# v13.net
KiCad netlist of a schematic drawn in EAGLE
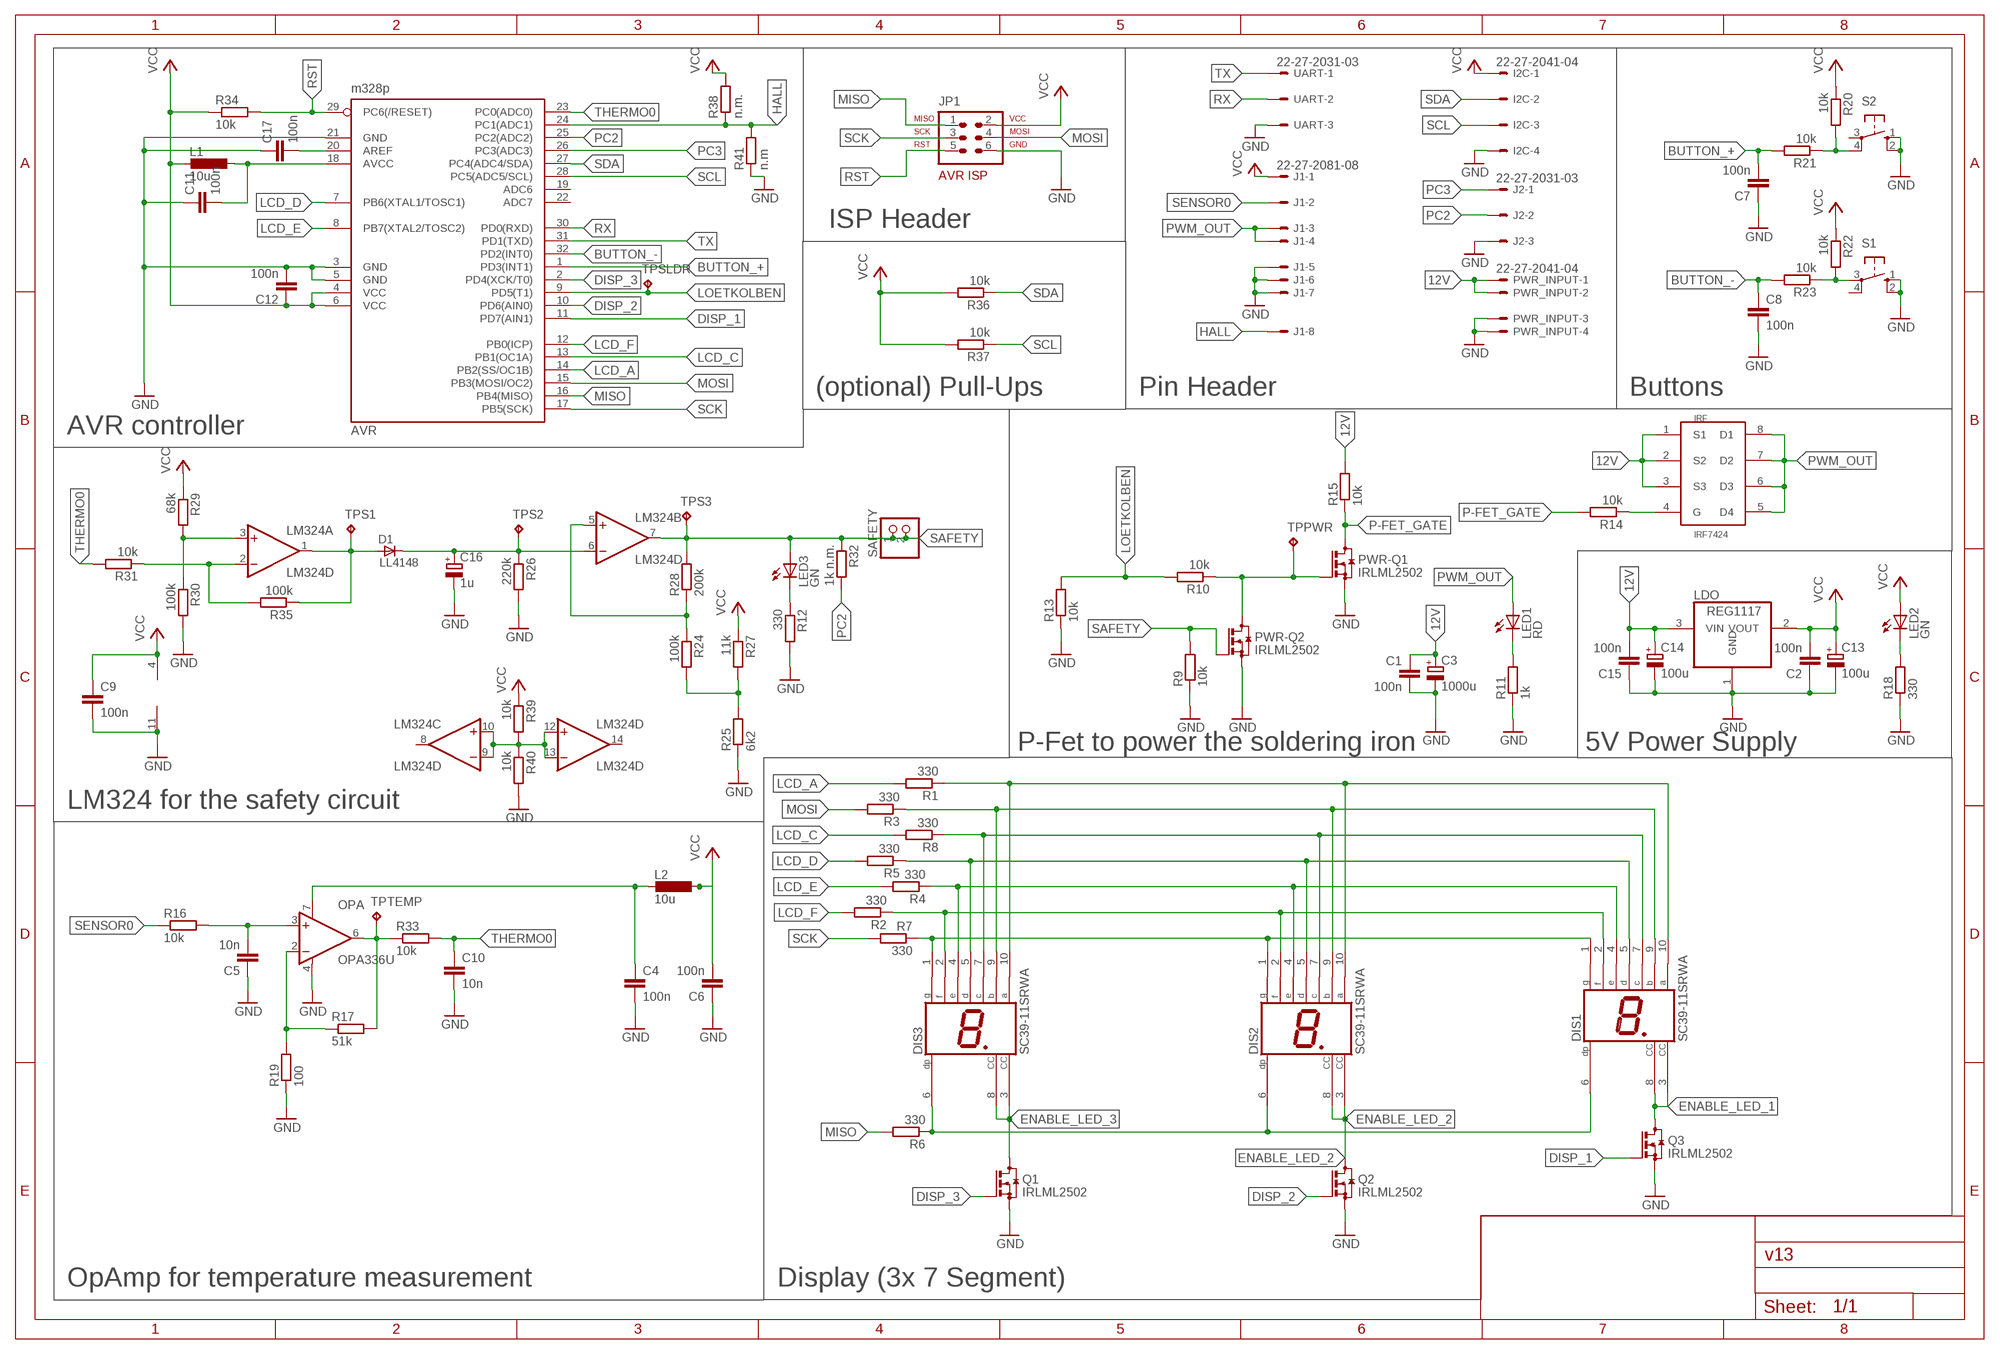
[diagram p0: schematic, sheet 1]

(export (version "E")
  (design (tool "Eeschema 10.0.6"))
  (components
    (comp (ref "AVR")
      (value "m328p")
      (footprint "eagle-import:TQFP32-08")
      (fields (field (name "MPN") "ATMEGA8-16AU"))
      (libsource (lib "eagle-import") (part "MEGA8-AI"))
    )
    (comp (ref "C1")
      (value "100n")
      (footprint "eagle-import:C0603")
      (libsource (lib "eagle-import") (part "C-EUC0603"))
    )
    (comp (ref "C2")
      (value "100n")
      (footprint "eagle-import:C0603")
      (libsource (lib "eagle-import") (part "C-EUC0603"))
    )
    (comp (ref "C3")
      (value "1000u")
      (footprint "eagle-import:E5-13")
      (libsource (lib "eagle-import") (part "CPOL-EUE5-13"))
    )
    (comp (ref "C4")
      (value "100n")
      (footprint "eagle-import:C0603")
      (libsource (lib "eagle-import") (part "C-EUC0603"))
    )
    (comp (ref "C5")
      (value "10n")
      (footprint "eagle-import:C0603")
      (libsource (lib "eagle-import") (part "C-EUC0603"))
    )
    (comp (ref "C6")
      (value "100n")
      (footprint "eagle-import:C0603")
      (libsource (lib "eagle-import") (part "C-EUC0603"))
    )
    (comp (ref "C7")
      (value "100n")
      (footprint "eagle-import:C0603")
      (libsource (lib "eagle-import") (part "C-EUC0603"))
    )
    (comp (ref "C8")
      (value "100n")
      (footprint "eagle-import:C0603")
      (libsource (lib "eagle-import") (part "C-EUC0603"))
    )
    (comp (ref "C9")
      (value "100n")
      (footprint "eagle-import:C0603")
      (libsource (lib "eagle-import") (part "C-EUC0603"))
    )
    (comp (ref "C10")
      (value "10n")
      (footprint "eagle-import:C0603")
      (libsource (lib "eagle-import") (part "C-EUC0603"))
    )
    (comp (ref "C11")
      (value "100n")
      (footprint "eagle-import:C0603")
      (libsource (lib "eagle-import") (part "C-EUC0603"))
    )
    (comp (ref "C12")
      (value "100n")
      (footprint "eagle-import:C0603")
      (libsource (lib "eagle-import") (part "C-EUC0603"))
    )
    (comp (ref "C13")
      (value "100u")
      (footprint "eagle-import:E2-5")
      (libsource (lib "eagle-import") (part "CPOL-EUE2-5"))
    )
    (comp (ref "C14")
      (value "100u")
      (footprint "eagle-import:E2-5")
      (libsource (lib "eagle-import") (part "CPOL-EUE2-5"))
    )
    (comp (ref "C15")
      (value "100n")
      (footprint "eagle-import:C0603")
      (libsource (lib "eagle-import") (part "C-EUC0603"))
    )
    (comp (ref "C16")
      (value "1u")
      (footprint "eagle-import:E2-5")
      (libsource (lib "eagle-import") (part "CPOL-EUE2-5"))
    )
    (comp (ref "C17")
      (value "100n")
      (footprint "eagle-import:C0603")
      (libsource (lib "eagle-import") (part "C-EUC0603"))
    )
    (comp (ref "D1")
      (value "LL4148")
      (footprint "eagle-import:SOD80_DO213AA_MINIMELF")
      (libsource (lib "eagle-import") (part "LL4148"))
    )
    (comp (ref "DIS1")
      (value "SC39-11SRWA")
      (footprint "eagle-import:HDSP-E")
      (libsource (lib "eagle-import") (part "SC39-11SRWA"))
    )
    (comp (ref "DIS2")
      (value "SC39-11SRWA")
      (footprint "eagle-import:HDSP-E")
      (libsource (lib "eagle-import") (part "SC39-11SRWA"))
    )
    (comp (ref "DIS3")
      (value "SC39-11SRWA")
      (footprint "eagle-import:HDSP-E")
      (libsource (lib "eagle-import") (part "SC39-11SRWA"))
    )
    (comp (ref "I2C")
      (value "22-27-2041-04")
      (footprint "eagle-import:6410-04")
      (libsource (lib "eagle-import") (part "22-?-0427-2041"))
    )
    (comp (ref "IRF")
      (value "IRF7424")
      (footprint "eagle-import:SO-08")
      (libsource (lib "eagle-import") (part "IRF7424"))
    )
    (comp (ref "J1")
      (value "22-27-2081-08")
      (footprint "eagle-import:6410-08")
      (libsource (lib "eagle-import") (part "22-?-0827-2081"))
    )
    (comp (ref "J2")
      (value "22-27-2031-03")
      (footprint "eagle-import:6410-03")
      (libsource (lib "eagle-import") (part "22-?-0327-2031"))
    )
    (comp (ref "JP1")
      (value "AVR-ISP-6VERT")
      (footprint "eagle-import:AVR-ISP-6")
      (libsource (lib "eagle-import") (part "AVR-ISP-6VERT"))
    )
    (comp (ref "L1")
      (value "10u")
      (footprint "eagle-import:L2825P")
      (libsource (lib "eagle-import") (part "L-EUL2825P"))
    )
    (comp (ref "L2")
      (value "10u")
      (footprint "eagle-import:L2825P")
      (libsource (lib "eagle-import") (part "L-EUL2825P"))
    )
    (comp (ref "LDO")
      (value "REG1117")
      (footprint "eagle-import:SOT223")
      (libsource (lib "eagle-import") (part "REG1117"))
    )
    (comp (ref "LED1")
      (value "RD")
      (footprint "eagle-import:CHIP-LED0805")
      (libsource (lib "eagle-import") (part "LEDCHIP-LED0805"))
    )
    (comp (ref "LED2")
      (value "GN")
      (footprint "eagle-import:CHIP-LED0805")
      (libsource (lib "eagle-import") (part "LEDCHIP-LED0805"))
    )
    (comp (ref "LED3")
      (value "GN")
      (footprint "eagle-import:CHIP-LED0805")
      (libsource (lib "eagle-import") (part "LEDCHIP-LED0805"))
    )
    (comp (ref "LM324")
      (value "LM324D")
      (footprint "eagle-import:SO14")
      (libsource (lib "eagle-import") (part "LM324D"))
    )
    (comp (ref "OPA")
      (value "OPA336U")
      (footprint "eagle-import:SO08")
      (fields (field (name "MF") "TEXAS INSTRUMENT CONNECTORS") (field (name "MPN") "OPA336UA"))
      (libsource (lib "eagle-import") (part "OPA336U"))
    )
    (comp (ref "PWR-Q1")
      (value "IRLML2502")
      (footprint "eagle-import:SOT23")
      (libsource (lib "eagle-import") (part "BSS123"))
    )
    (comp (ref "PWR-Q2")
      (value "IRLML2502")
      (footprint "eagle-import:SOT23")
      (libsource (lib "eagle-import") (part "BSS123"))
    )
    (comp (ref "PWR_INPUT")
      (value "22-27-2041-04")
      (footprint "eagle-import:6410-04")
      (libsource (lib "eagle-import") (part "22-?-0427-2041"))
    )
    (comp (ref "Q1")
      (value "IRLML2502")
      (footprint "eagle-import:SOT23")
      (libsource (lib "eagle-import") (part "BSS123"))
    )
    (comp (ref "Q2")
      (value "IRLML2502")
      (footprint "eagle-import:SOT23")
      (libsource (lib "eagle-import") (part "BSS123"))
    )
    (comp (ref "Q3")
      (value "IRLML2502")
      (footprint "eagle-import:SOT23")
      (libsource (lib "eagle-import") (part "BSS123"))
    )
    (comp (ref "R1")
      (value "330")
      (footprint "eagle-import:R0603")
      (libsource (lib "eagle-import") (part "R-EU_R0603"))
    )
    (comp (ref "R2")
      (value "330")
      (footprint "eagle-import:R0603")
      (libsource (lib "eagle-import") (part "R-EU_R0603"))
    )
    (comp (ref "R3")
      (value "330")
      (footprint "eagle-import:R0603")
      (libsource (lib "eagle-import") (part "R-EU_R0603"))
    )
    (comp (ref "R4")
      (value "330")
      (footprint "eagle-import:R0603")
      (libsource (lib "eagle-import") (part "R-EU_R0603"))
    )
    (comp (ref "R5")
      (value "330")
      (footprint "eagle-import:R0603")
      (libsource (lib "eagle-import") (part "R-EU_R0603"))
    )
    (comp (ref "R6")
      (value "330")
      (footprint "eagle-import:R0603")
      (libsource (lib "eagle-import") (part "R-EU_R0603"))
    )
    (comp (ref "R7")
      (value "330")
      (footprint "eagle-import:R0603")
      (libsource (lib "eagle-import") (part "R-EU_R0603"))
    )
    (comp (ref "R8")
      (value "330")
      (footprint "eagle-import:R0603")
      (libsource (lib "eagle-import") (part "R-EU_R0603"))
    )
    (comp (ref "R9")
      (value "10k")
      (footprint "eagle-import:R0603")
      (libsource (lib "eagle-import") (part "R-EU_R0603"))
    )
    (comp (ref "R10")
      (value "10k")
      (footprint "eagle-import:R0603")
      (libsource (lib "eagle-import") (part "R-EU_R0603"))
    )
    (comp (ref "R11")
      (value "1k")
      (footprint "eagle-import:R0603")
      (libsource (lib "eagle-import") (part "R-EU_R0603"))
    )
    (comp (ref "R12")
      (value "330")
      (footprint "eagle-import:R0603")
      (libsource (lib "eagle-import") (part "R-EU_R0603"))
    )
    (comp (ref "R13")
      (value "10k")
      (footprint "eagle-import:R0603")
      (libsource (lib "eagle-import") (part "R-EU_R0603"))
    )
    (comp (ref "R14")
      (value "10k")
      (footprint "eagle-import:R0603")
      (libsource (lib "eagle-import") (part "R-EU_R0603"))
    )
    (comp (ref "R15")
      (value "10k")
      (footprint "eagle-import:R0603")
      (libsource (lib "eagle-import") (part "R-EU_R0603"))
    )
    (comp (ref "R16")
      (value "10k")
      (footprint "eagle-import:R0603")
      (libsource (lib "eagle-import") (part "R-EU_R0603"))
    )
    (comp (ref "R17")
      (value "51k")
      (footprint "eagle-import:R0603")
      (libsource (lib "eagle-import") (part "R-EU_R0603"))
    )
    (comp (ref "R18")
      (value "330")
      (footprint "eagle-import:R0603")
      (libsource (lib "eagle-import") (part "R-EU_R0603"))
    )
    (comp (ref "R19")
      (value "100")
      (footprint "eagle-import:R0603")
      (libsource (lib "eagle-import") (part "R-EU_R0603"))
    )
    (comp (ref "R20")
      (value "10k")
      (footprint "eagle-import:R0603")
      (libsource (lib "eagle-import") (part "R-EU_R0603"))
    )
    (comp (ref "R21")
      (value "10k")
      (footprint "eagle-import:R0603")
      (libsource (lib "eagle-import") (part "R-EU_R0603"))
    )
    (comp (ref "R22")
      (value "10k")
      (footprint "eagle-import:R0603")
      (libsource (lib "eagle-import") (part "R-EU_R0603"))
    )
    (comp (ref "R23")
      (value "10k")
      (footprint "eagle-import:R0603")
      (libsource (lib "eagle-import") (part "R-EU_R0603"))
    )
    (comp (ref "R24")
      (value "100k")
      (footprint "eagle-import:R0603")
      (libsource (lib "eagle-import") (part "R-EU_R0603"))
    )
    (comp (ref "R25")
      (value "6k2")
      (footprint "eagle-import:R0603")
      (libsource (lib "eagle-import") (part "R-EU_R0603"))
    )
    (comp (ref "R26")
      (value "220k")
      (footprint "eagle-import:R0603")
      (libsource (lib "eagle-import") (part "R-EU_R0603"))
    )
    (comp (ref "R27")
      (value "11k")
      (footprint "eagle-import:R0603")
      (libsource (lib "eagle-import") (part "R-EU_R0603"))
    )
    (comp (ref "R28")
      (value "200k")
      (footprint "eagle-import:R0603")
      (libsource (lib "eagle-import") (part "R-EU_R0603"))
    )
    (comp (ref "R29")
      (value "68k")
      (footprint "eagle-import:R0603")
      (libsource (lib "eagle-import") (part "R-EU_R0603"))
    )
    (comp (ref "R30")
      (value "100k")
      (footprint "eagle-import:R0603")
      (libsource (lib "eagle-import") (part "R-EU_R0603"))
    )
    (comp (ref "R31")
      (value "10k")
      (footprint "eagle-import:R0603")
      (libsource (lib "eagle-import") (part "R-EU_R0603"))
    )
    (comp (ref "R32")
      (value "1k n.m.")
      (footprint "eagle-import:R0603")
      (libsource (lib "eagle-import") (part "R-EU_R0603"))
    )
    (comp (ref "R33")
      (value "10k")
      (footprint "eagle-import:R0603")
      (libsource (lib "eagle-import") (part "R-EU_R0603"))
    )
    (comp (ref "R34")
      (value "10k")
      (footprint "eagle-import:R0603")
      (libsource (lib "eagle-import") (part "R-EU_R0603"))
    )
    (comp (ref "R35")
      (value "100k")
      (footprint "eagle-import:R0603")
      (libsource (lib "eagle-import") (part "R-EU_R0603"))
    )
    (comp (ref "R36")
      (value "10k")
      (footprint "eagle-import:R0603")
      (libsource (lib "eagle-import") (part "R-EU_R0603"))
    )
    (comp (ref "R37")
      (value "10k")
      (footprint "eagle-import:R0603")
      (libsource (lib "eagle-import") (part "R-EU_R0603"))
    )
    (comp (ref "R38")
      (value "n.m.")
      (footprint "eagle-import:R0603")
      (libsource (lib "eagle-import") (part "R-EU_R0603"))
    )
    (comp (ref "R39")
      (value "10k")
      (footprint "eagle-import:R0603")
      (libsource (lib "eagle-import") (part "R-EU_R0603"))
    )
    (comp (ref "R40")
      (value "10k")
      (footprint "eagle-import:R0603")
      (libsource (lib "eagle-import") (part "R-EU_R0603"))
    )
    (comp (ref "R41")
      (value "n.m")
      (footprint "eagle-import:R0603")
      (libsource (lib "eagle-import") (part "R-EU_R0603"))
    )
    (comp (ref "S1")
      (value "10-XX")
      (footprint "eagle-import:B3F-10XX")
      (fields (field (name "MPN") "B3F-1000"))
      (libsource (lib "eagle-import") (part "10-XX"))
    )
    (comp (ref "S2")
      (value "10-XX")
      (footprint "eagle-import:B3F-10XX")
      (fields (field (name "MPN") "B3F-1000"))
      (libsource (lib "eagle-import") (part "10-XX"))
    )
    (comp (ref "SAFETY")
      (value "PINHD-1X2")
      (footprint "eagle-import:1X02")
      (libsource (lib "eagle-import") (part "PINHD-1X2"))
    )
    (comp (ref "TPPWR")
      (value "TPB1,27")
      (footprint "eagle-import:B1,27")
      (libsource (lib "eagle-import") (part "TPB1,27"))
    )
    (comp (ref "TPS1")
      (value "TPB1,27")
      (footprint "eagle-import:B1,27")
      (libsource (lib "eagle-import") (part "TPB1,27"))
    )
    (comp (ref "TPS2")
      (value "TPB1,27")
      (footprint "eagle-import:B1,27")
      (libsource (lib "eagle-import") (part "TPB1,27"))
    )
    (comp (ref "TPS3")
      (value "TPB1,27")
      (footprint "eagle-import:B1,27")
      (libsource (lib "eagle-import") (part "TPB1,27"))
    )
    (comp (ref "TPSLDR")
      (value "TPB1,27")
      (footprint "eagle-import:B1,27")
      (libsource (lib "eagle-import") (part "TPB1,27"))
    )
    (comp (ref "TPTEMP")
      (value "TPB1,27")
      (footprint "eagle-import:B1,27")
      (libsource (lib "eagle-import") (part "TPB1,27"))
    )
    (comp (ref "UART")
      (value "22-27-2031-03")
      (footprint "eagle-import:6410-03")
      (libsource (lib "eagle-import") (part "22-?-0327-2031"))
    )
  )
  (nets
    (net (code "1") (name "12V") (class "Default")
      (node (ref "C1") (pin "1") (pinfunction "1_1") (pintype "passive"))
      (node (ref "C14") (pin "+") (pinfunction "+_+") (pintype "passive"))
      (node (ref "C15") (pin "2") (pinfunction "2_2") (pintype "passive"))
      (node (ref "C3") (pin "+") (pinfunction "+_+") (pintype "passive"))
      (node (ref "IRF") (pin "1") (pinfunction "S1_1") (pintype "bidirectional"))
      (node (ref "IRF") (pin "2") (pinfunction "S2_2") (pintype "bidirectional"))
      (node (ref "IRF") (pin "3") (pinfunction "S3_3") (pintype "bidirectional"))
      (node (ref "LDO") (pin "3") (pinfunction "VIN_3") (pintype "input"))
      (node (ref "PWR_INPUT") (pin "1") (pinfunction "S_1") (pintype "passive"))
      (node (ref "PWR_INPUT") (pin "2") (pinfunction "S_2") (pintype "passive"))
      (node (ref "R15") (pin "2") (pinfunction "2_2") (pintype "passive"))
    )
    (net (code "2") (name "BUTTON_+") (class "Default")
      (node (ref "AVR") (pin "1") (pinfunction "PD3(INT1)_1") (pintype "bidirectional"))
      (node (ref "C7") (pin "2") (pinfunction "2_2") (pintype "passive"))
      (node (ref "R21") (pin "2") (pinfunction "2_2") (pintype "passive"))
    )
    (net (code "3") (name "BUTTON_-") (class "Default")
      (node (ref "AVR") (pin "32") (pinfunction "PD2(INT0)_32") (pintype "bidirectional"))
      (node (ref "C8") (pin "1") (pinfunction "1_1") (pintype "passive"))
      (node (ref "R23") (pin "2") (pinfunction "2_2") (pintype "passive"))
    )
    (net (code "4") (name "DISP_1") (class "Default")
      (node (ref "AVR") (pin "11") (pinfunction "PD7(AIN1)_11") (pintype "bidirectional"))
      (node (ref "Q3") (pin "1") (pinfunction "G_1") (pintype "passive"))
    )
    (net (code "5") (name "DISP_2") (class "Default")
      (node (ref "AVR") (pin "10") (pinfunction "PD6(AIN0)_10") (pintype "bidirectional"))
      (node (ref "Q2") (pin "1") (pinfunction "G_1") (pintype "passive"))
    )
    (net (code "6") (name "DISP_3") (class "Default")
      (node (ref "AVR") (pin "2") (pinfunction "PD4(XCK/T0)_2") (pintype "bidirectional"))
      (node (ref "Q1") (pin "1") (pinfunction "G_1") (pintype "passive"))
    )
    (net (code "7") (name "ENABLE_LED_1") (class "Default")
      (node (ref "DIS1") (pin "3") (pinfunction "CC_3") (pintype "passive"))
      (node (ref "DIS1") (pin "8") (pinfunction "CC_8") (pintype "passive"))
      (node (ref "Q3") (pin "3") (pinfunction "D_3") (pintype "passive"))
    )
    (net (code "8") (name "ENABLE_LED_2") (class "Default")
      (node (ref "DIS2") (pin "3") (pinfunction "CC_3") (pintype "passive"))
      (node (ref "DIS2") (pin "8") (pinfunction "CC_8") (pintype "passive"))
      (node (ref "Q2") (pin "3") (pinfunction "D_3") (pintype "passive"))
    )
    (net (code "9") (name "ENABLE_LED_3") (class "Default")
      (node (ref "DIS3") (pin "3") (pinfunction "CC_3") (pintype "passive"))
      (node (ref "DIS3") (pin "8") (pinfunction "CC_8") (pintype "passive"))
      (node (ref "Q1") (pin "3") (pinfunction "D_3") (pintype "passive"))
    )
    (net (code "10") (name "GND") (class "Default")
      (node (ref "AVR") (pin "21") (pinfunction "GND_21") (pintype "power_in"))
      (node (ref "AVR") (pin "3") (pinfunction "GND_3") (pintype "power_in"))
      (node (ref "AVR") (pin "5") (pinfunction "GND_5") (pintype "power_in"))
      (node (ref "C1") (pin "2") (pinfunction "2_2") (pintype "passive"))
      (node (ref "C10") (pin "2") (pinfunction "2_2") (pintype "passive"))
      (node (ref "C11") (pin "1") (pinfunction "1_1") (pintype "passive"))
      (node (ref "C12") (pin "2") (pinfunction "2_2") (pintype "passive"))
      (node (ref "C13") (pin "-") (pinfunction "-_-") (pintype "passive"))
      (node (ref "C14") (pin "-") (pinfunction "-_-") (pintype "passive"))
      (node (ref "C15") (pin "1") (pinfunction "1_1") (pintype "passive"))
      (node (ref "C16") (pin "-") (pinfunction "-_-") (pintype "passive"))
      (node (ref "C17") (pin "1") (pinfunction "1_1") (pintype "passive"))
      (node (ref "C2") (pin "1") (pinfunction "1_1") (pintype "passive"))
      (node (ref "C3") (pin "-") (pinfunction "-_-") (pintype "passive"))
      (node (ref "C4") (pin "2") (pinfunction "2_2") (pintype "passive"))
      (node (ref "C5") (pin "1") (pinfunction "1_1") (pintype "passive"))
      (node (ref "C6") (pin "1") (pinfunction "1_1") (pintype "passive"))
      (node (ref "C7") (pin "1") (pinfunction "1_1") (pintype "passive"))
      (node (ref "C8") (pin "2") (pinfunction "2_2") (pintype "passive"))
      (node (ref "C9") (pin "2") (pinfunction "2_2") (pintype "passive"))
      (node (ref "I2C") (pin "4") (pinfunction "S_4") (pintype "passive"))
      (node (ref "J1") (pin "5") (pinfunction "S_5") (pintype "passive"))
      (node (ref "J1") (pin "6") (pinfunction "S_6") (pintype "passive"))
      (node (ref "J1") (pin "7") (pinfunction "S_7") (pintype "passive"))
      (node (ref "J2") (pin "3") (pinfunction "S_3") (pintype "passive"))
      (node (ref "JP1") (pin "6") (pinfunction "6_6") (pintype "passive"))
      (node (ref "LDO") (pin "1") (pinfunction "GND_1") (pintype "power_in"))
      (node (ref "LM324") (pin "11") (pinfunction "V-_11") (pintype "power_in"))
      (node (ref "OPA") (pin "4") (pinfunction "V-_4") (pintype "power_in"))
      (node (ref "PWR-Q1") (pin "2") (pinfunction "S_2") (pintype "passive"))
      (node (ref "PWR-Q2") (pin "2") (pinfunction "S_2") (pintype "passive"))
      (node (ref "PWR_INPUT") (pin "3") (pinfunction "S_3") (pintype "passive"))
      (node (ref "PWR_INPUT") (pin "4") (pinfunction "S_4") (pintype "passive"))
      (node (ref "Q1") (pin "2") (pinfunction "S_2") (pintype "passive"))
      (node (ref "Q2") (pin "2") (pinfunction "S_2") (pintype "passive"))
      (node (ref "Q3") (pin "2") (pinfunction "S_2") (pintype "passive"))
      (node (ref "R11") (pin "1") (pinfunction "1_1") (pintype "passive"))
      (node (ref "R12") (pin "2") (pinfunction "2_2") (pintype "passive"))
      (node (ref "R13") (pin "1") (pinfunction "1_1") (pintype "passive"))
      (node (ref "R18") (pin "1") (pinfunction "1_1") (pintype "passive"))
      (node (ref "R19") (pin "1") (pinfunction "1_1") (pintype "passive"))
      (node (ref "R25") (pin "1") (pinfunction "1_1") (pintype "passive"))
      (node (ref "R26") (pin "2") (pinfunction "2_2") (pintype "passive"))
      (node (ref "R30") (pin "2") (pinfunction "2_2") (pintype "passive"))
      (node (ref "R40") (pin "2") (pinfunction "2_2") (pintype "passive"))
      (node (ref "R41") (pin "1") (pinfunction "1_1") (pintype "passive"))
      (node (ref "R9") (pin "1") (pinfunction "1_1") (pintype "passive"))
      (node (ref "S1") (pin "1") (pinfunction "S_1") (pintype "passive"))
      (node (ref "S1") (pin "2") (pinfunction "S1_2") (pintype "passive"))
      (node (ref "S2") (pin "1") (pinfunction "S_1") (pintype "passive"))
      (node (ref "S2") (pin "2") (pinfunction "S1_2") (pintype "passive"))
      (node (ref "UART") (pin "3") (pinfunction "S_3") (pintype "passive"))
    )
    (net (code "11") (name "HALL") (class "Default")
      (node (ref "AVR") (pin "24") (pinfunction "PC1(ADC1)_24") (pintype "bidirectional"))
      (node (ref "J1") (pin "8") (pinfunction "S_8") (pintype "passive"))
      (node (ref "R38") (pin "1") (pinfunction "1_1") (pintype "passive"))
      (node (ref "R41") (pin "2") (pinfunction "2_2") (pintype "passive"))
    )
    (net (code "12") (name "LCD_A") (class "Default")
      (node (ref "AVR") (pin "14") (pinfunction "PB2(SS/OC1B)_14") (pintype "bidirectional"))
      (node (ref "R1") (pin "2") (pinfunction "2_2") (pintype "passive"))
    )
    (net (code "13") (name "LCD_C") (class "Default")
      (node (ref "AVR") (pin "13") (pinfunction "PB1(OC1A)_13") (pintype "bidirectional"))
      (node (ref "R8") (pin "2") (pinfunction "2_2") (pintype "passive"))
    )
    (net (code "14") (name "LCD_D") (class "Default")
      (node (ref "AVR") (pin "7") (pinfunction "PB6(XTAL1/TOSC1)_7") (pintype "bidirectional"))
      (node (ref "R5") (pin "2") (pinfunction "2_2") (pintype "passive"))
    )
    (net (code "15") (name "LCD_E") (class "Default")
      (node (ref "AVR") (pin "8") (pinfunction "PB7(XTAL2/TOSC2)_8") (pintype "bidirectional"))
      (node (ref "R4") (pin "2") (pinfunction "2_2") (pintype "passive"))
    )
    (net (code "16") (name "LCD_F") (class "Default")
      (node (ref "AVR") (pin "12") (pinfunction "PB0(ICP)_12") (pintype "bidirectional"))
      (node (ref "R2") (pin "2") (pinfunction "2_2") (pintype "passive"))
    )
    (net (code "17") (name "LOETKOLBEN") (class "Default")
      (node (ref "AVR") (pin "9") (pinfunction "PD5(T1)_9") (pintype "bidirectional"))
      (node (ref "R10") (pin "2") (pinfunction "2_2") (pintype "passive"))
      (node (ref "R13") (pin "2") (pinfunction "2_2") (pintype "passive"))
      (node (ref "TPSLDR") (pin "TP") (pinfunction "TP_TP") (pintype "input"))
    )
    (net (code "18") (name "MISO") (class "Default")
      (node (ref "AVR") (pin "16") (pinfunction "PB4(MISO)_16") (pintype "bidirectional"))
      (node (ref "JP1") (pin "1") (pinfunction "1_1") (pintype "passive"))
      (node (ref "R6") (pin "2") (pinfunction "2_2") (pintype "passive"))
    )
    (net (code "19") (name "MOSI") (class "Default")
      (node (ref "AVR") (pin "15") (pinfunction "PB3(MOSI/OC2)_15") (pintype "bidirectional"))
      (node (ref "JP1") (pin "4") (pinfunction "4_4") (pintype "passive"))
      (node (ref "R3") (pin "2") (pinfunction "2_2") (pintype "passive"))
    )
    (net (code "20") (name "Net-(AVR-AREF)") (class "Default")
      (node (ref "AVR") (pin "20") (pinfunction "AREF_20") (pintype "passive"))
      (node (ref "C17") (pin "2") (pinfunction "2_2") (pintype "passive"))
    )
    (net (code "21") (name "Net-(AVR-AVCC)") (class "Default")
      (node (ref "AVR") (pin "18") (pinfunction "AVCC_18") (pintype "power_in"))
      (node (ref "C11") (pin "2") (pinfunction "2_2") (pintype "passive"))
      (node (ref "L1") (pin "1") (pinfunction "1_1") (pintype "passive"))
    )
    (net (code "22") (name "Net-(DIS1-A)") (class "Default")
      (node (ref "DIS1") (pin "10") (pinfunction "A_10") (pintype "passive"))
      (node (ref "DIS2") (pin "10") (pinfunction "A_10") (pintype "passive"))
      (node (ref "DIS3") (pin "10") (pinfunction "A_10") (pintype "passive"))
      (node (ref "R1") (pin "1") (pinfunction "1_1") (pintype "passive"))
    )
    (net (code "23") (name "Net-(DIS1-B)") (class "Default")
      (node (ref "DIS1") (pin "9") (pinfunction "B_9") (pintype "passive"))
      (node (ref "DIS2") (pin "9") (pinfunction "B_9") (pintype "passive"))
      (node (ref "DIS3") (pin "9") (pinfunction "B_9") (pintype "passive"))
      (node (ref "R3") (pin "1") (pinfunction "1_1") (pintype "passive"))
    )
    (net (code "24") (name "Net-(DIS1-C)") (class "Default")
      (node (ref "DIS1") (pin "7") (pinfunction "C_7") (pintype "passive"))
      (node (ref "DIS2") (pin "7") (pinfunction "C_7") (pintype "passive"))
      (node (ref "DIS3") (pin "7") (pinfunction "C_7") (pintype "passive"))
      (node (ref "R8") (pin "1") (pinfunction "1_1") (pintype "passive"))
    )
    (net (code "25") (name "Net-(DIS1-D)") (class "Default")
      (node (ref "DIS1") (pin "5") (pinfunction "D_5") (pintype "passive"))
      (node (ref "DIS2") (pin "5") (pinfunction "D_5") (pintype "passive"))
      (node (ref "DIS3") (pin "5") (pinfunction "D_5") (pintype "passive"))
      (node (ref "R5") (pin "1") (pinfunction "1_1") (pintype "passive"))
    )
    (net (code "26") (name "Net-(DIS1-DP)") (class "Default")
      (node (ref "DIS1") (pin "6") (pinfunction "DP_6") (pintype "passive"))
      (node (ref "DIS2") (pin "6") (pinfunction "DP_6") (pintype "passive"))
      (node (ref "DIS3") (pin "6") (pinfunction "DP_6") (pintype "passive"))
      (node (ref "R6") (pin "1") (pinfunction "1_1") (pintype "passive"))
    )
    (net (code "27") (name "Net-(DIS1-E)") (class "Default")
      (node (ref "DIS1") (pin "4") (pinfunction "E_4") (pintype "passive"))
      (node (ref "DIS2") (pin "4") (pinfunction "E_4") (pintype "passive"))
      (node (ref "DIS3") (pin "4") (pinfunction "E_4") (pintype "passive"))
      (node (ref "R4") (pin "1") (pinfunction "1_1") (pintype "passive"))
    )
    (net (code "28") (name "Net-(DIS1-F)") (class "Default")
      (node (ref "DIS1") (pin "2") (pinfunction "F_2") (pintype "passive"))
      (node (ref "DIS2") (pin "2") (pinfunction "F_2") (pintype "passive"))
      (node (ref "DIS3") (pin "2") (pinfunction "F_2") (pintype "passive"))
      (node (ref "R2") (pin "1") (pinfunction "1_1") (pintype "passive"))
    )
    (net (code "29") (name "Net-(DIS1-G)") (class "Default")
      (node (ref "DIS1") (pin "1") (pinfunction "G_1") (pintype "passive"))
      (node (ref "DIS2") (pin "1") (pinfunction "G_1") (pintype "passive"))
      (node (ref "DIS3") (pin "1") (pinfunction "G_1") (pintype "passive"))
      (node (ref "R7") (pin "1") (pinfunction "1_1") (pintype "passive"))
    )
    (net (code "30") (name "Net-(IRF-G)") (class "Default")
      (node (ref "IRF") (pin "4") (pinfunction "G_4") (pintype "bidirectional"))
      (node (ref "R14") (pin "1") (pinfunction "1_1") (pintype "passive"))
    )
    (net (code "31") (name "Net-(LED1-PadC)") (class "Default")
      (node (ref "LED1") (pin "C") (pinfunction "C_C") (pintype "passive"))
      (node (ref "R11") (pin "2") (pinfunction "2_2") (pintype "passive"))
    )
    (net (code "32") (name "Net-(LED2-PadC)") (class "Default")
      (node (ref "LED2") (pin "C") (pinfunction "C_C") (pintype "passive"))
      (node (ref "R18") (pin "2") (pinfunction "2_2") (pintype "passive"))
    )
    (net (code "33") (name "Net-(LED3-PadC)") (class "Default")
      (node (ref "LED3") (pin "C") (pinfunction "C_C") (pintype "passive"))
      (node (ref "R12") (pin "1") (pinfunction "1_1") (pintype "passive"))
    )
    (net (code "34") (name "Net-(LM324A-+IN)") (class "Default")
      (node (ref "LM324") (pin "3") (pinfunction "+IN_3") (pintype "input"))
      (node (ref "R29") (pin "2") (pinfunction "2_2") (pintype "passive"))
      (node (ref "R30") (pin "1") (pinfunction "1_1") (pintype "passive"))
    )
    (net (code "35") (name "Net-(LM324A--IN)") (class "Default")
      (node (ref "LM324") (pin "2") (pinfunction "-IN_2") (pintype "input"))
      (node (ref "R31") (pin "1") (pinfunction "1_1") (pintype "passive"))
      (node (ref "R35") (pin "2") (pinfunction "2_2") (pintype "passive"))
    )
    (net (code "36") (name "Net-(LM324A-OUT)") (class "Default")
      (node (ref "D1") (pin "A") (pinfunction "A_A") (pintype "passive"))
      (node (ref "LM324") (pin "1") (pinfunction "OUT_1") (pintype "output"))
      (node (ref "R35") (pin "1") (pinfunction "1_1") (pintype "passive"))
      (node (ref "TPS1") (pin "TP") (pinfunction "TP_TP") (pintype "input"))
    )
    (net (code "37") (name "Net-(LM324B-+IN)") (class "Default")
      (node (ref "LM324") (pin "5") (pinfunction "+IN_5") (pintype "input"))
      (node (ref "R24") (pin "1") (pinfunction "1_1") (pintype "passive"))
      (node (ref "R28") (pin "1") (pinfunction "1_1") (pintype "passive"))
    )
    (net (code "38") (name "Net-(LM324B--IN)") (class "Default")
      (node (ref "C16") (pin "+") (pinfunction "+_+") (pintype "passive"))
      (node (ref "D1") (pin "C") (pinfunction "C_C") (pintype "passive"))
      (node (ref "LM324") (pin "6") (pinfunction "-IN_6") (pintype "input"))
      (node (ref "R26") (pin "1") (pinfunction "1_1") (pintype "passive"))
      (node (ref "TPS2") (pin "TP") (pinfunction "TP_TP") (pintype "input"))
    )
    (net (code "39") (name "Net-(LM324C-+IN)") (class "Default")
      (node (ref "LM324") (pin "10") (pinfunction "+IN_10") (pintype "input"))
      (node (ref "LM324") (pin "12") (pinfunction "+IN_12") (pintype "input"))
      (node (ref "LM324") (pin "13") (pinfunction "-IN_13") (pintype "input"))
      (node (ref "LM324") (pin "9") (pinfunction "-IN_9") (pintype "input"))
      (node (ref "R39") (pin "2") (pinfunction "2_2") (pintype "passive"))
      (node (ref "R40") (pin "1") (pinfunction "1_1") (pintype "passive"))
    )
    (net (code "40") (name "Net-(OPA-+IN)") (class "Default")
      (node (ref "C5") (pin "2") (pinfunction "2_2") (pintype "passive"))
      (node (ref "OPA") (pin "3") (pinfunction "+IN_3") (pintype "input"))
      (node (ref "R16") (pin "2") (pinfunction "2_2") (pintype "passive"))
    )
    (net (code "41") (name "Net-(OPA--IN)") (class "Default")
      (node (ref "OPA") (pin "2") (pinfunction "-IN_2") (pintype "input"))
      (node (ref "R17") (pin "1") (pinfunction "1_1") (pintype "passive"))
      (node (ref "R19") (pin "2") (pinfunction "2_2") (pintype "passive"))
    )
    (net (code "42") (name "Net-(OPA-OUT)") (class "Default")
      (node (ref "OPA") (pin "6") (pinfunction "OUT_6") (pintype "output"))
      (node (ref "R17") (pin "2") (pinfunction "2_2") (pintype "passive"))
      (node (ref "R33") (pin "1") (pinfunction "1_1") (pintype "passive"))
      (node (ref "TPTEMP") (pin "TP") (pinfunction "TP_TP") (pintype "input"))
    )
    (net (code "43") (name "Net-(OPA-V+)") (class "Default")
      (node (ref "C4") (pin "1") (pinfunction "1_1") (pintype "passive"))
      (node (ref "L2") (pin "2") (pinfunction "2_2") (pintype "passive"))
      (node (ref "OPA") (pin "7") (pinfunction "V+_7") (pintype "power_in"))
    )
    (net (code "44") (name "Net-(PWR-Q1-G)") (class "Default")
      (node (ref "PWR-Q1") (pin "1") (pinfunction "G_1") (pintype "passive"))
      (node (ref "PWR-Q2") (pin "3") (pinfunction "D_3") (pintype "passive"))
      (node (ref "R10") (pin "1") (pinfunction "1_1") (pintype "passive"))
      (node (ref "TPPWR") (pin "TP") (pinfunction "TP_TP") (pintype "input"))
    )
    (net (code "45") (name "Net-(R24-Pad2)") (class "Default")
      (node (ref "R24") (pin "2") (pinfunction "2_2") (pintype "passive"))
      (node (ref "R25") (pin "2") (pinfunction "2_2") (pintype "passive"))
      (node (ref "R27") (pin "2") (pinfunction "2_2") (pintype "passive"))
    )
    (net (code "46") (name "Net-(S1-P)") (class "Default")
      (node (ref "R22") (pin "2") (pinfunction "2_2") (pintype "passive"))
      (node (ref "R23") (pin "1") (pinfunction "1_1") (pintype "passive"))
      (node (ref "S1") (pin "3") (pinfunction "P_3") (pintype "passive"))
    )
    (net (code "47") (name "Net-(S2-P1)") (class "Default")
      (node (ref "R20") (pin "2") (pinfunction "2_2") (pintype "passive"))
      (node (ref "R21") (pin "1") (pinfunction "1_1") (pintype "passive"))
      (node (ref "S2") (pin "4") (pinfunction "P1_4") (pintype "passive"))
    )
    (net (code "48") (name "P-FET_GATE") (class "Default")
      (node (ref "PWR-Q1") (pin "3") (pinfunction "D_3") (pintype "passive"))
      (node (ref "R14") (pin "2") (pinfunction "2_2") (pintype "passive"))
      (node (ref "R15") (pin "1") (pinfunction "1_1") (pintype "passive"))
    )
    (net (code "49") (name "PC2") (class "Default")
      (node (ref "AVR") (pin "25") (pinfunction "PC2(ADC2)_25") (pintype "bidirectional"))
      (node (ref "J2") (pin "2") (pinfunction "S_2") (pintype "passive"))
      (node (ref "R32") (pin "2") (pinfunction "2_2") (pintype "passive"))
    )
    (net (code "50") (name "PC3") (class "Default")
      (node (ref "AVR") (pin "26") (pinfunction "PC3(ADC3)_26") (pintype "bidirectional"))
      (node (ref "J2") (pin "1") (pinfunction "S_1") (pintype "passive"))
    )
    (net (code "51") (name "PWM_OUT") (class "Default")
      (node (ref "IRF") (pin "5") (pinfunction "D4_5") (pintype "bidirectional"))
      (node (ref "IRF") (pin "6") (pinfunction "D3_6") (pintype "bidirectional"))
      (node (ref "IRF") (pin "7") (pinfunction "D2_7") (pintype "bidirectional"))
      (node (ref "IRF") (pin "8") (pinfunction "D1_8") (pintype "bidirectional"))
      (node (ref "J1") (pin "3") (pinfunction "S_3") (pintype "passive"))
      (node (ref "J1") (pin "4") (pinfunction "S_4") (pintype "passive"))
      (node (ref "LED1") (pin "A") (pinfunction "A_A") (pintype "passive"))
    )
    (net (code "52") (name "RST") (class "Default")
      (node (ref "AVR") (pin "29") (pinfunction "PC6(/RESET)_29") (pintype "bidirectional"))
      (node (ref "JP1") (pin "5") (pinfunction "5_5") (pintype "passive"))
      (node (ref "R34") (pin "2") (pinfunction "2_2") (pintype "passive"))
    )
    (net (code "53") (name "RX") (class "Default")
      (node (ref "AVR") (pin "30") (pinfunction "PD0(RXD)_30") (pintype "bidirectional"))
      (node (ref "UART") (pin "2") (pinfunction "S_2") (pintype "passive"))
    )
    (net (code "54") (name "SAFETY") (class "Default")
      (node (ref "LED3") (pin "A") (pinfunction "A_A") (pintype "passive"))
      (node (ref "LM324") (pin "7") (pinfunction "OUT_7") (pintype "output"))
      (node (ref "PWR-Q2") (pin "1") (pinfunction "G_1") (pintype "passive"))
      (node (ref "R28") (pin "2") (pinfunction "2_2") (pintype "passive"))
      (node (ref "R32") (pin "1") (pinfunction "1_1") (pintype "passive"))
      (node (ref "R9") (pin "2") (pinfunction "2_2") (pintype "passive"))
      (node (ref "SAFETY") (pin "1") (pinfunction "1_1") (pintype "passive"))
      (node (ref "SAFETY") (pin "2") (pinfunction "2_2") (pintype "passive"))
      (node (ref "TPS3") (pin "TP") (pinfunction "TP_TP") (pintype "input"))
    )
    (net (code "55") (name "SCK") (class "Default")
      (node (ref "AVR") (pin "17") (pinfunction "PB5(SCK)_17") (pintype "bidirectional"))
      (node (ref "JP1") (pin "3") (pinfunction "3_3") (pintype "passive"))
      (node (ref "R7") (pin "2") (pinfunction "2_2") (pintype "passive"))
    )
    (net (code "56") (name "SCL") (class "Default")
      (node (ref "AVR") (pin "28") (pinfunction "PC5(ADC5/SCL)_28") (pintype "bidirectional"))
      (node (ref "I2C") (pin "3") (pinfunction "S_3") (pintype "passive"))
      (node (ref "R37") (pin "1") (pinfunction "1_1") (pintype "passive"))
    )
    (net (code "57") (name "SDA") (class "Default")
      (node (ref "AVR") (pin "27") (pinfunction "PC4(ADC4/SDA)_27") (pintype "bidirectional"))
      (node (ref "I2C") (pin "2") (pinfunction "S_2") (pintype "passive"))
      (node (ref "R36") (pin "1") (pinfunction "1_1") (pintype "passive"))
    )
    (net (code "58") (name "SENSOR0") (class "Default")
      (node (ref "J1") (pin "2") (pinfunction "S_2") (pintype "passive"))
      (node (ref "R16") (pin "1") (pinfunction "1_1") (pintype "passive"))
    )
    (net (code "59") (name "THERMO0") (class "Default")
      (node (ref "AVR") (pin "23") (pinfunction "PC0(ADC0)_23") (pintype "bidirectional"))
      (node (ref "C10") (pin "1") (pinfunction "1_1") (pintype "passive"))
      (node (ref "R31") (pin "2") (pinfunction "2_2") (pintype "passive"))
      (node (ref "R33") (pin "2") (pinfunction "2_2") (pintype "passive"))
    )
    (net (code "60") (name "TX") (class "Default")
      (node (ref "AVR") (pin "31") (pinfunction "PD1(TXD)_31") (pintype "bidirectional"))
      (node (ref "UART") (pin "1") (pinfunction "S_1") (pintype "passive"))
    )
    (net (code "61") (name "VCC") (class "Default")
      (node (ref "AVR") (pin "4") (pinfunction "VCC_4") (pintype "power_in"))
      (node (ref "AVR") (pin "6") (pinfunction "VCC_6") (pintype "power_in"))
      (node (ref "C12") (pin "1") (pinfunction "1_1") (pintype "passive"))
      (node (ref "C13") (pin "+") (pinfunction "+_+") (pintype "passive"))
      (node (ref "C2") (pin "2") (pinfunction "2_2") (pintype "passive"))
      (node (ref "C6") (pin "2") (pinfunction "2_2") (pintype "passive"))
      (node (ref "C9") (pin "1") (pinfunction "1_1") (pintype "passive"))
      (node (ref "I2C") (pin "1") (pinfunction "S_1") (pintype "passive"))
      (node (ref "J1") (pin "1") (pinfunction "S_1") (pintype "passive"))
      (node (ref "JP1") (pin "2") (pinfunction "2_2") (pintype "passive"))
      (node (ref "L1") (pin "2") (pinfunction "2_2") (pintype "passive"))
      (node (ref "L2") (pin "1") (pinfunction "1_1") (pintype "passive"))
      (node (ref "LDO") (pin "2") (pinfunction "VOUT_2") (pintype "output"))
      (node (ref "LED2") (pin "A") (pinfunction "A_A") (pintype "passive"))
      (node (ref "LM324") (pin "4") (pinfunction "V+_4") (pintype "power_in"))
      (node (ref "R20") (pin "1") (pinfunction "1_1") (pintype "passive"))
      (node (ref "R22") (pin "1") (pinfunction "1_1") (pintype "passive"))
      (node (ref "R27") (pin "1") (pinfunction "1_1") (pintype "passive"))
      (node (ref "R29") (pin "1") (pinfunction "1_1") (pintype "passive"))
      (node (ref "R34") (pin "1") (pinfunction "1_1") (pintype "passive"))
      (node (ref "R36") (pin "2") (pinfunction "2_2") (pintype "passive"))
      (node (ref "R37") (pin "2") (pinfunction "2_2") (pintype "passive"))
      (node (ref "R38") (pin "2") (pinfunction "2_2") (pintype "passive"))
      (node (ref "R39") (pin "1") (pinfunction "1_1") (pintype "passive"))
    )
    (net (code "62") (name "unconnected-(AVR-ADC6-Pad19)") (class "Default")
      (node (ref "AVR") (pin "19") (pinfunction "ADC6_19") (pintype "bidirectional"))
    )
    (net (code "63") (name "unconnected-(AVR-ADC7-Pad22)") (class "Default")
      (node (ref "AVR") (pin "22") (pinfunction "ADC7_22") (pintype "bidirectional"))
    )
    (net (code "64") (name "unconnected-(LM324C-OUT-Pad8)") (class "Default")
      (node (ref "LM324") (pin "8") (pinfunction "OUT_8") (pintype "output"))
    )
    (net (code "65") (name "unconnected-(LM324D-OUT-Pad14)") (class "Default")
      (node (ref "LM324") (pin "14") (pinfunction "OUT_14") (pintype "output"))
    )
    (net (code "66") (name "unconnected-(S1-P1-Pad4)") (class "Default")
      (node (ref "S1") (pin "4") (pinfunction "P1_4") (pintype "passive"))
    )
    (net (code "67") (name "unconnected-(S2-P-Pad3)") (class "Default")
      (node (ref "S2") (pin "3") (pinfunction "P_3") (pintype "passive"))
    )
  )
)
